# addon.net
KiCad netlist of a schematic drawn in EAGLE
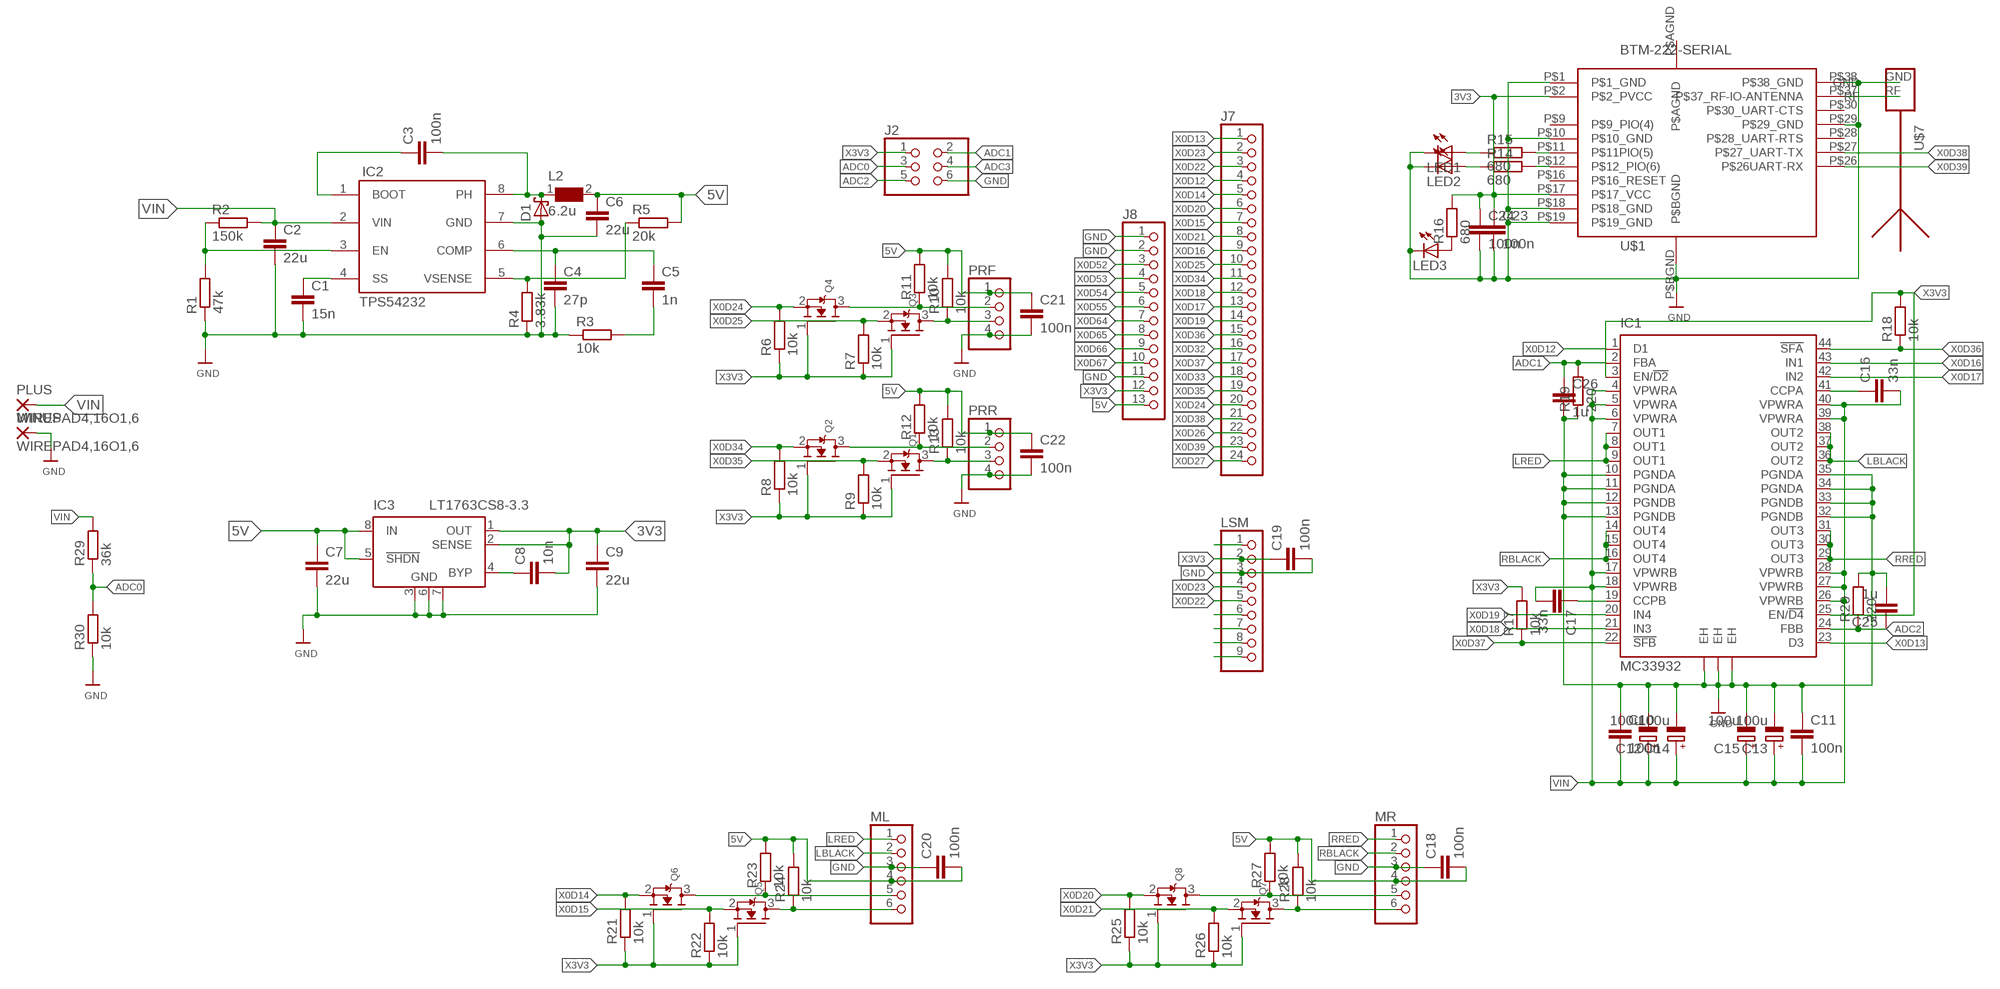
[diagram p0: schematic, sheet 1]

(export (version "E")
  (design (tool "Eeschema 10.0.6"))
  (components
    (comp (ref "C1")
      (value "15n")
      (footprint "eagle-import:C0603")
      (libsource (lib "eagle-import") (part "C-EUC0603"))
    )
    (comp (ref "C2")
      (value "22u")
      (footprint "eagle-import:C1210")
      (libsource (lib "eagle-import") (part "C-EUC1210"))
    )
    (comp (ref "C3")
      (value "100n")
      (footprint "eagle-import:C0603")
      (libsource (lib "eagle-import") (part "C-EUC0603"))
    )
    (comp (ref "C4")
      (value "27p")
      (footprint "eagle-import:C0603")
      (libsource (lib "eagle-import") (part "C-EUC0603"))
    )
    (comp (ref "C5")
      (value "1n")
      (footprint "eagle-import:C0603")
      (libsource (lib "eagle-import") (part "C-EUC0603"))
    )
    (comp (ref "C6")
      (value "22u")
      (footprint "eagle-import:C1206")
      (libsource (lib "eagle-import") (part "C-EUC1206"))
    )
    (comp (ref "C7")
      (value "22u")
      (footprint "eagle-import:C0603")
      (libsource (lib "eagle-import") (part "C-EUC0603"))
    )
    (comp (ref "C8")
      (value "10n")
      (footprint "eagle-import:C0603")
      (libsource (lib "eagle-import") (part "C-EUC0603"))
    )
    (comp (ref "C9")
      (value "22u")
      (footprint "eagle-import:C0603")
      (libsource (lib "eagle-import") (part "C-EUC0603"))
    )
    (comp (ref "C10")
      (value "100n")
      (footprint "eagle-import:C0603")
      (libsource (lib "eagle-import") (part "C-EUC0603"))
    )
    (comp (ref "C11")
      (value "100n")
      (footprint "eagle-import:C0603")
      (libsource (lib "eagle-import") (part "C-EUC0603"))
    )
    (comp (ref "C12")
      (value "100u")
      (footprint "eagle-import:D_7343-31R")
      (libsource (lib "eagle-import") (part "CPOL-EUD/7343-31R"))
    )
    (comp (ref "C13")
      (value "100u")
      (footprint "eagle-import:D_7343-31R")
      (libsource (lib "eagle-import") (part "CPOL-EUD/7343-31R"))
    )
    (comp (ref "C14")
      (value "100u")
      (footprint "eagle-import:D_7343-31R")
      (libsource (lib "eagle-import") (part "CPOL-EUD/7343-31R"))
    )
    (comp (ref "C15")
      (value "100u")
      (footprint "eagle-import:D_7343-31R")
      (libsource (lib "eagle-import") (part "CPOL-EUD/7343-31R"))
    )
    (comp (ref "C16")
      (value "33n")
      (footprint "eagle-import:C0603")
      (libsource (lib "eagle-import") (part "C-EUC0603"))
    )
    (comp (ref "C17")
      (value "33n")
      (footprint "eagle-import:C0603")
      (libsource (lib "eagle-import") (part "C-EUC0603"))
    )
    (comp (ref "C18")
      (value "100n")
      (footprint "eagle-import:C0603")
      (libsource (lib "eagle-import") (part "C-EUC0603"))
    )
    (comp (ref "C19")
      (value "100n")
      (footprint "eagle-import:C0603")
      (libsource (lib "eagle-import") (part "C-EUC0603"))
    )
    (comp (ref "C20")
      (value "100n")
      (footprint "eagle-import:C0603")
      (libsource (lib "eagle-import") (part "C-EUC0603"))
    )
    (comp (ref "C21")
      (value "100n")
      (footprint "eagle-import:C0603")
      (libsource (lib "eagle-import") (part "C-EUC0603"))
    )
    (comp (ref "C22")
      (value "100n")
      (footprint "eagle-import:C0603")
      (libsource (lib "eagle-import") (part "C-EUC0603"))
    )
    (comp (ref "C23")
      (value "100n")
      (footprint "eagle-import:C0603")
      (libsource (lib "eagle-import") (part "C-EUC0603"))
    )
    (comp (ref "C24")
      (value "100n")
      (footprint "eagle-import:C0603")
      (libsource (lib "eagle-import") (part "C-EUC0603"))
    )
    (comp (ref "C25")
      (value "1u")
      (footprint "eagle-import:C0603")
      (libsource (lib "eagle-import") (part "C-EUC0603"))
    )
    (comp (ref "C26")
      (value "1u")
      (footprint "eagle-import:C0603")
      (libsource (lib "eagle-import") (part "C-EUC0603"))
    )
    (comp (ref "D1")
      (value "SCHOTTKY-DIODESMD")
      (footprint "eagle-import:SMB")
      (libsource (lib "eagle-import") (part "SCHOTTKY-DIODESMD"))
    )
    (comp (ref "IC1")
      (value "MC33932")
      (footprint "eagle-import:HSOP44")
      (fields (field (name "MPN") "MC33932VW"))
      (libsource (lib "eagle-import") (part "MC33932"))
    )
    (comp (ref "IC2")
      (value "TPS54232")
      (footprint "eagle-import:YOURITRONICS_SO8")
      (libsource (lib "eagle-import") (part "YOURITRONICS_TPS54232"))
    )
    (comp (ref "IC3")
      (value "LT1763CS8-3.3")
      (footprint "eagle-import:SOIC8")
      (libsource (lib "eagle-import") (part "LT1763CS8-3.3"))
    )
    (comp (ref "J2")
      (value "PINHD-2X3")
      (footprint "eagle-import:2X03")
      (libsource (lib "eagle-import") (part "PINHD-2X3"))
    )
    (comp (ref "J7")
      (value "PINHD-1X24")
      (footprint "eagle-import:1X24")
      (libsource (lib "eagle-import") (part "PINHD-1X24"))
    )
    (comp (ref "J8")
      (value "PINHD-1X13")
      (footprint "eagle-import:1X13")
      (libsource (lib "eagle-import") (part "PINHD-1X13"))
    )
    (comp (ref "L2")
      (value "6.2u")
      (footprint "eagle-import:EAGLELIBRARY_WUERTH_ELEKTRONIK_EISOS_VERSION_6_WE-TPC_6823")
      (libsource (lib "eagle-import") (part "EAGLELIBRARY_WUERTH_ELEKTRONIK_EISOS_VERSION_6_WE-TPC_6823"))
    )
    (comp (ref "LED1")
      (value "LEDCHIPLED_0603")
      (footprint "eagle-import:CHIPLED_0603")
      (libsource (lib "eagle-import") (part "LEDCHIPLED_0603"))
    )
    (comp (ref "LED2")
      (value "LEDCHIPLED_0603")
      (footprint "eagle-import:CHIPLED_0603")
      (libsource (lib "eagle-import") (part "LEDCHIPLED_0603"))
    )
    (comp (ref "LED3")
      (value "LEDCHIPLED_0603")
      (footprint "eagle-import:CHIPLED_0603")
      (libsource (lib "eagle-import") (part "LEDCHIPLED_0603"))
    )
    (comp (ref "LSM")
      (value "PINHD-1X9")
      (footprint "eagle-import:1X09")
      (libsource (lib "eagle-import") (part "PINHD-1X9"))
    )
    (comp (ref "MINUS")
      (value "WIREPAD4,16O1,6")
      (footprint "eagle-import:4,16O1,6")
      (libsource (lib "eagle-import") (part "WIREPAD4,16O1,6"))
    )
    (comp (ref "ML")
      (value "PINHD-1X6")
      (footprint "eagle-import:1X06")
      (libsource (lib "eagle-import") (part "PINHD-1X6"))
    )
    (comp (ref "MR")
      (value "PINHD-1X6")
      (footprint "eagle-import:1X06")
      (libsource (lib "eagle-import") (part "PINHD-1X6"))
    )
    (comp (ref "PLUS")
      (value "WIREPAD4,16O1,6")
      (footprint "eagle-import:4,16O1,6")
      (libsource (lib "eagle-import") (part "WIREPAD4,16O1,6"))
    )
    (comp (ref "PRF")
      (value "PINHD-1X4")
      (footprint "eagle-import:1X04")
      (libsource (lib "eagle-import") (part "PINHD-1X4"))
    )
    (comp (ref "PRR")
      (value "PINHD-1X4")
      (footprint "eagle-import:1X04")
      (libsource (lib "eagle-import") (part "PINHD-1X4"))
    )
    (comp (ref "Q1")
      (value "MOSFET-NREFLOW")
      (footprint "eagle-import:SOT23-R")
      (libsource (lib "eagle-import") (part "MOSFET-NREFLOW"))
    )
    (comp (ref "Q2")
      (value "MOSFET-NREFLOW")
      (footprint "eagle-import:SOT23-R")
      (libsource (lib "eagle-import") (part "MOSFET-NREFLOW"))
    )
    (comp (ref "Q3")
      (value "MOSFET-NREFLOW")
      (footprint "eagle-import:SOT23-R")
      (libsource (lib "eagle-import") (part "MOSFET-NREFLOW"))
    )
    (comp (ref "Q4")
      (value "MOSFET-NREFLOW")
      (footprint "eagle-import:SOT23-R")
      (libsource (lib "eagle-import") (part "MOSFET-NREFLOW"))
    )
    (comp (ref "Q5")
      (value "MOSFET-NREFLOW")
      (footprint "eagle-import:SOT23-R")
      (libsource (lib "eagle-import") (part "MOSFET-NREFLOW"))
    )
    (comp (ref "Q6")
      (value "MOSFET-NREFLOW")
      (footprint "eagle-import:SOT23-R")
      (libsource (lib "eagle-import") (part "MOSFET-NREFLOW"))
    )
    (comp (ref "Q7")
      (value "MOSFET-NREFLOW")
      (footprint "eagle-import:SOT23-R")
      (libsource (lib "eagle-import") (part "MOSFET-NREFLOW"))
    )
    (comp (ref "Q8")
      (value "MOSFET-NREFLOW")
      (footprint "eagle-import:SOT23-R")
      (libsource (lib "eagle-import") (part "MOSFET-NREFLOW"))
    )
    (comp (ref "R1")
      (value "47k")
      (footprint "eagle-import:R0603")
      (libsource (lib "eagle-import") (part "R-EU_R0603"))
    )
    (comp (ref "R2")
      (value "150k")
      (footprint "eagle-import:R0603")
      (libsource (lib "eagle-import") (part "R-EU_R0603"))
    )
    (comp (ref "R3")
      (value "10k")
      (footprint "eagle-import:R0603")
      (libsource (lib "eagle-import") (part "R-EU_R0603"))
    )
    (comp (ref "R4")
      (value "3.83k")
      (footprint "eagle-import:R0603")
      (libsource (lib "eagle-import") (part "R-EU_R0603"))
    )
    (comp (ref "R5")
      (value "20k")
      (footprint "eagle-import:R0603")
      (libsource (lib "eagle-import") (part "R-EU_R0603"))
    )
    (comp (ref "R6")
      (value "10k")
      (footprint "eagle-import:R0603")
      (libsource (lib "eagle-import") (part "R-EU_R0603"))
    )
    (comp (ref "R7")
      (value "10k")
      (footprint "eagle-import:R0603")
      (libsource (lib "eagle-import") (part "R-EU_R0603"))
    )
    (comp (ref "R8")
      (value "10k")
      (footprint "eagle-import:R0603")
      (libsource (lib "eagle-import") (part "R-EU_R0603"))
    )
    (comp (ref "R9")
      (value "10k")
      (footprint "eagle-import:R0603")
      (libsource (lib "eagle-import") (part "R-EU_R0603"))
    )
    (comp (ref "R10")
      (value "10k")
      (footprint "eagle-import:R0603")
      (libsource (lib "eagle-import") (part "R-EU_R0603"))
    )
    (comp (ref "R11")
      (value "10k")
      (footprint "eagle-import:R0603")
      (libsource (lib "eagle-import") (part "R-EU_R0603"))
    )
    (comp (ref "R12")
      (value "10k")
      (footprint "eagle-import:R0603")
      (libsource (lib "eagle-import") (part "R-EU_R0603"))
    )
    (comp (ref "R13")
      (value "10k")
      (footprint "eagle-import:R0603")
      (libsource (lib "eagle-import") (part "R-EU_R0603"))
    )
    (comp (ref "R14")
      (value "680")
      (footprint "eagle-import:R0603")
      (libsource (lib "eagle-import") (part "R-EU_R0603"))
    )
    (comp (ref "R15")
      (value "680")
      (footprint "eagle-import:R0603")
      (libsource (lib "eagle-import") (part "R-EU_R0603"))
    )
    (comp (ref "R16")
      (value "680")
      (footprint "eagle-import:R0603")
      (libsource (lib "eagle-import") (part "R-EU_R0603"))
    )
    (comp (ref "R17")
      (value "10k")
      (footprint "eagle-import:R0603")
      (libsource (lib "eagle-import") (part "R-EU_R0603"))
    )
    (comp (ref "R18")
      (value "10k")
      (footprint "eagle-import:R0603")
      (libsource (lib "eagle-import") (part "R-EU_R0603"))
    )
    (comp (ref "R19")
      (value "220")
      (footprint "eagle-import:R0603")
      (libsource (lib "eagle-import") (part "R-EU_R0603"))
    )
    (comp (ref "R20")
      (value "220")
      (footprint "eagle-import:R0603")
      (libsource (lib "eagle-import") (part "R-EU_R0603"))
    )
    (comp (ref "R21")
      (value "10k")
      (footprint "eagle-import:R0603")
      (libsource (lib "eagle-import") (part "R-EU_R0603"))
    )
    (comp (ref "R22")
      (value "10k")
      (footprint "eagle-import:R0603")
      (libsource (lib "eagle-import") (part "R-EU_R0603"))
    )
    (comp (ref "R23")
      (value "10k")
      (footprint "eagle-import:R0603")
      (libsource (lib "eagle-import") (part "R-EU_R0603"))
    )
    (comp (ref "R24")
      (value "10k")
      (footprint "eagle-import:R0603")
      (libsource (lib "eagle-import") (part "R-EU_R0603"))
    )
    (comp (ref "R25")
      (value "10k")
      (footprint "eagle-import:R0603")
      (libsource (lib "eagle-import") (part "R-EU_R0603"))
    )
    (comp (ref "R26")
      (value "10k")
      (footprint "eagle-import:R0603")
      (libsource (lib "eagle-import") (part "R-EU_R0603"))
    )
    (comp (ref "R27")
      (value "10k")
      (footprint "eagle-import:R0603")
      (libsource (lib "eagle-import") (part "R-EU_R0603"))
    )
    (comp (ref "R28")
      (value "10k")
      (footprint "eagle-import:R0603")
      (libsource (lib "eagle-import") (part "R-EU_R0603"))
    )
    (comp (ref "R29")
      (value "36k")
      (footprint "eagle-import:R0603")
      (libsource (lib "eagle-import") (part "R-EU_R0603"))
    )
    (comp (ref "R30")
      (value "10k")
      (footprint "eagle-import:R0603")
      (libsource (lib "eagle-import") (part "R-EU_R0603"))
    )
    (comp (ref "U$1")
      (value "BTM-222-SERIAL")
      (footprint "eagle-import:BTM-222")
      (libsource (lib "eagle-import") (part "BTM-222-SERIAL"))
    )
    (comp (ref "U$7")
      (value "ANTENNA_1RIGHT")
      (footprint "eagle-import:SWRA117D_RIGHT")
      (libsource (lib "eagle-import") (part "ANTENNA_1RIGHT"))
    )
  )
  (nets
    (net (code "1") (name "/P$AGND") (class "Default")
      (node (ref "U$1") (pin "P$AGND") (pinfunction "P$AGND_P$AGND") (pintype "power_in"))
    )
    (net (code "2") (name "3V3") (class "Default")
      (node (ref "C23") (pin "1") (pinfunction "1_1") (pintype "passive"))
      (node (ref "C24") (pin "1") (pinfunction "1_1") (pintype "passive"))
      (node (ref "C8") (pin "2") (pinfunction "2_2") (pintype "passive"))
      (node (ref "C9") (pin "1") (pinfunction "1_1") (pintype "passive"))
      (node (ref "IC3") (pin "1") (pinfunction "OUT_1") (pintype "passive"))
      (node (ref "IC3") (pin "2") (pinfunction "SENSE_2") (pintype "input"))
      (node (ref "R16") (pin "2") (pinfunction "2_2") (pintype "passive"))
      (node (ref "U$1") (pin "P$17") (pinfunction "P$17_VCC_P$17") (pintype "power_in"))
      (node (ref "U$1") (pin "P$2") (pinfunction "P$2_PVCC_P$2") (pintype "power_in"))
    )
    (net (code "3") (name "5V") (class "Default")
      (node (ref "C18") (pin "2") (pinfunction "2_2") (pintype "passive"))
      (node (ref "C20") (pin "2") (pinfunction "2_2") (pintype "passive"))
      (node (ref "C21") (pin "1") (pinfunction "1_1") (pintype "passive"))
      (node (ref "C22") (pin "1") (pinfunction "1_1") (pintype "passive"))
      (node (ref "C6") (pin "1") (pinfunction "1_1") (pintype "passive"))
      (node (ref "C7") (pin "1") (pinfunction "1_1") (pintype "passive"))
      (node (ref "IC3") (pin "5") (pinfunction "~{SHDN}_5") (pintype "input"))
      (node (ref "IC3") (pin "8") (pinfunction "IN_8") (pintype "input"))
      (node (ref "J8") (pin "13") (pinfunction "13_13") (pintype "passive"))
      (node (ref "L2") (pin "2") (pinfunction "2_2") (pintype "passive"))
      (node (ref "ML") (pin "4") (pinfunction "4_4") (pintype "passive"))
      (node (ref "MR") (pin "4") (pinfunction "4_4") (pintype "passive"))
      (node (ref "PRF") (pin "1") (pinfunction "1_1") (pintype "passive"))
      (node (ref "PRR") (pin "1") (pinfunction "1_1") (pintype "passive"))
      (node (ref "R10") (pin "2") (pinfunction "2_2") (pintype "passive"))
      (node (ref "R11") (pin "2") (pinfunction "2_2") (pintype "passive"))
      (node (ref "R12") (pin "2") (pinfunction "2_2") (pintype "passive"))
      (node (ref "R13") (pin "2") (pinfunction "2_2") (pintype "passive"))
      (node (ref "R23") (pin "2") (pinfunction "2_2") (pintype "passive"))
      (node (ref "R24") (pin "2") (pinfunction "2_2") (pintype "passive"))
      (node (ref "R27") (pin "2") (pinfunction "2_2") (pintype "passive"))
      (node (ref "R28") (pin "2") (pinfunction "2_2") (pintype "passive"))
      (node (ref "R5") (pin "2") (pinfunction "2_2") (pintype "passive"))
    )
    (net (code "4") (name "ADC0") (class "Default")
      (node (ref "J2") (pin "3") (pinfunction "3_3") (pintype "passive"))
      (node (ref "R29") (pin "1") (pinfunction "1_1") (pintype "passive"))
      (node (ref "R30") (pin "2") (pinfunction "2_2") (pintype "passive"))
    )
    (net (code "5") (name "ADC1") (class "Default")
      (node (ref "C26") (pin "1") (pinfunction "1_1") (pintype "passive"))
      (node (ref "IC1") (pin "2") (pinfunction "FBA_2") (pintype "output"))
      (node (ref "J2") (pin "2") (pinfunction "2_2") (pintype "passive"))
      (node (ref "R19") (pin "2") (pinfunction "2_2") (pintype "passive"))
    )
    (net (code "6") (name "ADC2") (class "Default")
      (node (ref "C25") (pin "1") (pinfunction "1_1") (pintype "passive"))
      (node (ref "IC1") (pin "24") (pinfunction "FBB_24") (pintype "output"))
      (node (ref "J2") (pin "5") (pinfunction "5_5") (pintype "passive"))
      (node (ref "R20") (pin "1") (pinfunction "1_1") (pintype "passive"))
    )
    (net (code "7") (name "ADC3") (class "Default")
      (node (ref "J2") (pin "4") (pinfunction "4_4") (pintype "passive"))
    )
    (net (code "8") (name "GND") (class "Default")
      (node (ref "C1") (pin "2") (pinfunction "2_2") (pintype "passive"))
      (node (ref "C10") (pin "1") (pinfunction "1_1") (pintype "passive"))
      (node (ref "C11") (pin "1") (pinfunction "1_1") (pintype "passive"))
      (node (ref "C12") (pin "-") (pinfunction "-_-") (pintype "passive"))
      (node (ref "C13") (pin "-") (pinfunction "-_-") (pintype "passive"))
      (node (ref "C14") (pin "-") (pinfunction "-_-") (pintype "passive"))
      (node (ref "C15") (pin "-") (pinfunction "-_-") (pintype "passive"))
      (node (ref "C18") (pin "1") (pinfunction "1_1") (pintype "passive"))
      (node (ref "C19") (pin "2") (pinfunction "2_2") (pintype "passive"))
      (node (ref "C2") (pin "2") (pinfunction "2_2") (pintype "passive"))
      (node (ref "C20") (pin "1") (pinfunction "1_1") (pintype "passive"))
      (node (ref "C21") (pin "2") (pinfunction "2_2") (pintype "passive"))
      (node (ref "C22") (pin "2") (pinfunction "2_2") (pintype "passive"))
      (node (ref "C23") (pin "2") (pinfunction "2_2") (pintype "passive"))
      (node (ref "C24") (pin "2") (pinfunction "2_2") (pintype "passive"))
      (node (ref "C25") (pin "2") (pinfunction "2_2") (pintype "passive"))
      (node (ref "C26") (pin "2") (pinfunction "2_2") (pintype "passive"))
      (node (ref "C4") (pin "2") (pinfunction "2_2") (pintype "passive"))
      (node (ref "C6") (pin "2") (pinfunction "2_2") (pintype "passive"))
      (node (ref "C7") (pin "2") (pinfunction "2_2") (pintype "passive"))
      (node (ref "C9") (pin "2") (pinfunction "2_2") (pintype "passive"))
      (node (ref "D1") (pin "A") (pinfunction "A_A") (pintype "passive"))
      (node (ref "IC1") (pin "10") (pinfunction "PGNDA_10") (pintype "power_in"))
      (node (ref "IC1") (pin "11") (pinfunction "PGNDA_11") (pintype "power_in"))
      (node (ref "IC1") (pin "12") (pinfunction "PGNDB_12") (pintype "power_in"))
      (node (ref "IC1") (pin "13") (pinfunction "PGNDB_13") (pintype "power_in"))
      (node (ref "IC1") (pin "32") (pinfunction "PGNDB_32") (pintype "power_in"))
      (node (ref "IC1") (pin "33") (pinfunction "PGNDB_33") (pintype "power_in"))
      (node (ref "IC1") (pin "34") (pinfunction "PGNDA_34") (pintype "power_in"))
      (node (ref "IC1") (pin "35") (pinfunction "PGNDA_35") (pintype "power_in"))
      (node (ref "IC1") (pin "EH@1") (pinfunction "EH_EH@1") (pintype "passive"))
      (node (ref "IC1") (pin "EH@2") (pinfunction "EH_EH@2") (pintype "passive"))
      (node (ref "IC1") (pin "EH@3") (pinfunction "EH_EH@3") (pintype "passive"))
      (node (ref "IC2") (pin "7") (pinfunction "GND_7") (pintype "bidirectional"))
      (node (ref "IC3") (pin "3") (pinfunction "GND_3") (pintype "power_in"))
      (node (ref "IC3") (pin "6") (pinfunction "GND_6") (pintype "power_in"))
      (node (ref "IC3") (pin "7") (pinfunction "GND_7") (pintype "power_in"))
      (node (ref "J2") (pin "6") (pinfunction "6_6") (pintype "passive"))
      (node (ref "J8") (pin "1") (pinfunction "1_1") (pintype "passive"))
      (node (ref "J8") (pin "11") (pinfunction "11_11") (pintype "passive"))
      (node (ref "J8") (pin "2") (pinfunction "2_2") (pintype "passive"))
      (node (ref "LED1") (pin "C") (pinfunction "C_C") (pintype "passive"))
      (node (ref "LED2") (pin "C") (pinfunction "C_C") (pintype "passive"))
      (node (ref "LED3") (pin "C") (pinfunction "C_C") (pintype "passive"))
      (node (ref "LSM") (pin "3") (pinfunction "3_3") (pintype "passive"))
      (node (ref "MINUS") (pin "1") (pinfunction "P_1") (pintype "passive"))
      (node (ref "ML") (pin "3") (pinfunction "3_3") (pintype "passive"))
      (node (ref "MR") (pin "3") (pinfunction "3_3") (pintype "passive"))
      (node (ref "PRF") (pin "4") (pinfunction "4_4") (pintype "passive"))
      (node (ref "PRR") (pin "4") (pinfunction "4_4") (pintype "passive"))
      (node (ref "R1") (pin "1") (pinfunction "1_1") (pintype "passive"))
      (node (ref "R19") (pin "1") (pinfunction "1_1") (pintype "passive"))
      (node (ref "R20") (pin "2") (pinfunction "2_2") (pintype "passive"))
      (node (ref "R3") (pin "1") (pinfunction "1_1") (pintype "passive"))
      (node (ref "R30") (pin "1") (pinfunction "1_1") (pintype "passive"))
      (node (ref "R4") (pin "1") (pinfunction "1_1") (pintype "passive"))
      (node (ref "U$1") (pin "P$1") (pinfunction "P$1_GND_P$1") (pintype "power_in"))
      (node (ref "U$1") (pin "P$10") (pinfunction "P$10_GND_P$10") (pintype "power_in"))
      (node (ref "U$1") (pin "P$18") (pinfunction "P$18_GND_P$18") (pintype "power_in"))
      (node (ref "U$1") (pin "P$19") (pinfunction "P$19_GND_P$19") (pintype "power_in"))
      (node (ref "U$1") (pin "P$29") (pinfunction "P$29_GND_P$29") (pintype "power_in"))
      (node (ref "U$1") (pin "P$38") (pinfunction "P$38_GND_P$38") (pintype "power_in"))
      (node (ref "U$1") (pin "P$BGND") (pinfunction "P$BGND_P$BGND") (pintype "power_in"))
      (node (ref "U$7") (pin "GND") (pinfunction "GND_GND") (pintype "passive"))
    )
    (net (code "9") (name "LBLACK") (class "Default")
      (node (ref "IC1") (pin "36") (pinfunction "OUT2_36") (pintype "output"))
      (node (ref "IC1") (pin "37") (pinfunction "OUT2_37") (pintype "passive"))
      (node (ref "IC1") (pin "38") (pinfunction "OUT2_38") (pintype "passive"))
      (node (ref "ML") (pin "2") (pinfunction "2_2") (pintype "passive"))
    )
    (net (code "10") (name "LRED") (class "Default")
      (node (ref "IC1") (pin "7") (pinfunction "OUT1_7") (pintype "output"))
      (node (ref "IC1") (pin "8") (pinfunction "OUT1_8") (pintype "passive"))
      (node (ref "IC1") (pin "9") (pinfunction "OUT1_9") (pintype "passive"))
      (node (ref "ML") (pin "1") (pinfunction "1_1") (pintype "passive"))
    )
    (net (code "11") (name "Net-(C5-Pad2)") (class "Default")
      (node (ref "C5") (pin "2") (pinfunction "2_2") (pintype "passive"))
      (node (ref "R3") (pin "2") (pinfunction "2_2") (pintype "passive"))
    )
    (net (code "12") (name "Net-(IC1-CCPA)") (class "Default")
      (node (ref "C16") (pin "1") (pinfunction "1_1") (pintype "passive"))
      (node (ref "IC1") (pin "41") (pinfunction "CCPA_41") (pintype "output"))
    )
    (net (code "13") (name "Net-(IC1-CCPB)") (class "Default")
      (node (ref "C17") (pin "1") (pinfunction "1_1") (pintype "passive"))
      (node (ref "IC1") (pin "19") (pinfunction "CCPB_19") (pintype "output"))
    )
    (net (code "14") (name "Net-(IC2-BOOT)") (class "Default")
      (node (ref "C3") (pin "1") (pinfunction "1_1") (pintype "passive"))
      (node (ref "IC2") (pin "1") (pinfunction "BOOT_1") (pintype "bidirectional"))
    )
    (net (code "15") (name "Net-(IC2-COMP)") (class "Default")
      (node (ref "C4") (pin "1") (pinfunction "1_1") (pintype "passive"))
      (node (ref "C5") (pin "1") (pinfunction "1_1") (pintype "passive"))
      (node (ref "IC2") (pin "6") (pinfunction "COMP_6") (pintype "bidirectional"))
    )
    (net (code "16") (name "Net-(IC2-EN)") (class "Default")
      (node (ref "IC2") (pin "3") (pinfunction "EN_3") (pintype "bidirectional"))
      (node (ref "R1") (pin "2") (pinfunction "2_2") (pintype "passive"))
      (node (ref "R2") (pin "1") (pinfunction "1_1") (pintype "passive"))
    )
    (net (code "17") (name "Net-(IC2-PH)") (class "Default")
      (node (ref "C3") (pin "2") (pinfunction "2_2") (pintype "passive"))
      (node (ref "D1") (pin "C") (pinfunction "C_C") (pintype "passive"))
      (node (ref "IC2") (pin "8") (pinfunction "PH_8") (pintype "bidirectional"))
      (node (ref "L2") (pin "1") (pinfunction "1_1") (pintype "passive"))
    )
    (net (code "18") (name "Net-(IC2-SS)") (class "Default")
      (node (ref "C1") (pin "1") (pinfunction "1_1") (pintype "passive"))
      (node (ref "IC2") (pin "4") (pinfunction "SS_4") (pintype "bidirectional"))
    )
    (net (code "19") (name "Net-(IC2-VSENSE)") (class "Default")
      (node (ref "IC2") (pin "5") (pinfunction "VSENSE_5") (pintype "bidirectional"))
      (node (ref "R4") (pin "2") (pinfunction "2_2") (pintype "passive"))
      (node (ref "R5") (pin "1") (pinfunction "1_1") (pintype "passive"))
    )
    (net (code "20") (name "Net-(IC3-BYP)") (class "Default")
      (node (ref "C8") (pin "1") (pinfunction "1_1") (pintype "passive"))
      (node (ref "IC3") (pin "4") (pinfunction "BYP_4") (pintype "input"))
    )
    (net (code "21") (name "Net-(LED1-PadA)") (class "Default")
      (node (ref "LED1") (pin "A") (pinfunction "A_A") (pintype "passive"))
      (node (ref "R15") (pin "1") (pinfunction "1_1") (pintype "passive"))
    )
    (net (code "22") (name "Net-(LED2-PadA)") (class "Default")
      (node (ref "LED2") (pin "A") (pinfunction "A_A") (pintype "passive"))
      (node (ref "R14") (pin "1") (pinfunction "1_1") (pintype "passive"))
    )
    (net (code "23") (name "Net-(LED3-PadA)") (class "Default")
      (node (ref "LED3") (pin "A") (pinfunction "A_A") (pintype "passive"))
      (node (ref "R16") (pin "1") (pinfunction "1_1") (pintype "passive"))
    )
    (net (code "24") (name "Net-(Q1-D)") (class "Default")
      (node (ref "PRR") (pin "3") (pinfunction "3_3") (pintype "passive"))
      (node (ref "Q1") (pin "3") (pinfunction "D_3") (pintype "bidirectional"))
      (node (ref "R13") (pin "1") (pinfunction "1_1") (pintype "passive"))
    )
    (net (code "25") (name "Net-(Q2-D)") (class "Default")
      (node (ref "PRR") (pin "2") (pinfunction "2_2") (pintype "passive"))
      (node (ref "Q2") (pin "3") (pinfunction "D_3") (pintype "bidirectional"))
      (node (ref "R12") (pin "1") (pinfunction "1_1") (pintype "passive"))
    )
    (net (code "26") (name "Net-(Q3-D)") (class "Default")
      (node (ref "PRF") (pin "3") (pinfunction "3_3") (pintype "passive"))
      (node (ref "Q3") (pin "3") (pinfunction "D_3") (pintype "bidirectional"))
      (node (ref "R10") (pin "1") (pinfunction "1_1") (pintype "passive"))
    )
    (net (code "27") (name "Net-(Q4-D)") (class "Default")
      (node (ref "PRF") (pin "2") (pinfunction "2_2") (pintype "passive"))
      (node (ref "Q4") (pin "3") (pinfunction "D_3") (pintype "bidirectional"))
      (node (ref "R11") (pin "1") (pinfunction "1_1") (pintype "passive"))
    )
    (net (code "28") (name "Net-(Q5-D)") (class "Default")
      (node (ref "ML") (pin "6") (pinfunction "6_6") (pintype "passive"))
      (node (ref "Q5") (pin "3") (pinfunction "D_3") (pintype "bidirectional"))
      (node (ref "R24") (pin "1") (pinfunction "1_1") (pintype "passive"))
    )
    (net (code "29") (name "Net-(Q6-D)") (class "Default")
      (node (ref "ML") (pin "5") (pinfunction "5_5") (pintype "passive"))
      (node (ref "Q6") (pin "3") (pinfunction "D_3") (pintype "bidirectional"))
      (node (ref "R23") (pin "1") (pinfunction "1_1") (pintype "passive"))
    )
    (net (code "30") (name "Net-(Q7-D)") (class "Default")
      (node (ref "MR") (pin "6") (pinfunction "6_6") (pintype "passive"))
      (node (ref "Q7") (pin "3") (pinfunction "D_3") (pintype "bidirectional"))
      (node (ref "R28") (pin "1") (pinfunction "1_1") (pintype "passive"))
    )
    (net (code "31") (name "Net-(Q8-D)") (class "Default")
      (node (ref "MR") (pin "5") (pinfunction "5_5") (pintype "passive"))
      (node (ref "Q8") (pin "3") (pinfunction "D_3") (pintype "bidirectional"))
      (node (ref "R27") (pin "1") (pinfunction "1_1") (pintype "passive"))
    )
    (net (code "32") (name "Net-(U$1-P$11PIO(5))") (class "Default")
      (node (ref "R15") (pin "2") (pinfunction "2_2") (pintype "passive"))
      (node (ref "U$1") (pin "P$11") (pinfunction "P$11PIO(5)_P$11") (pintype "bidirectional"))
    )
    (net (code "33") (name "Net-(U$1-P$12_PIO(6))") (class "Default")
      (node (ref "R14") (pin "2") (pinfunction "2_2") (pintype "passive"))
      (node (ref "U$1") (pin "P$12") (pinfunction "P$12_PIO(6)_P$12") (pintype "bidirectional"))
    )
    (net (code "34") (name "Net-(U$1-P$37_RF-IO-ANTENNA)") (class "Default")
      (node (ref "U$1") (pin "P$37") (pinfunction "P$37_RF-IO-ANTENNA_P$37") (pintype "bidirectional"))
      (node (ref "U$7") (pin "RF") (pinfunction "RF_RF") (pintype "bidirectional"))
    )
    (net (code "35") (name "RBLACK") (class "Default")
      (node (ref "IC1") (pin "14") (pinfunction "OUT4_14") (pintype "output"))
      (node (ref "IC1") (pin "15") (pinfunction "OUT4_15") (pintype "passive"))
      (node (ref "IC1") (pin "16") (pinfunction "OUT4_16") (pintype "passive"))
      (node (ref "MR") (pin "2") (pinfunction "2_2") (pintype "passive"))
    )
    (net (code "36") (name "RRED") (class "Default")
      (node (ref "IC1") (pin "29") (pinfunction "OUT3_29") (pintype "output"))
      (node (ref "IC1") (pin "30") (pinfunction "OUT3_30") (pintype "passive"))
      (node (ref "IC1") (pin "31") (pinfunction "OUT3_31") (pintype "passive"))
      (node (ref "MR") (pin "1") (pinfunction "1_1") (pintype "passive"))
    )
    (net (code "37") (name "VIN") (class "Default")
      (node (ref "C10") (pin "2") (pinfunction "2_2") (pintype "passive"))
      (node (ref "C11") (pin "2") (pinfunction "2_2") (pintype "passive"))
      (node (ref "C12") (pin "+") (pinfunction "+_+") (pintype "passive"))
      (node (ref "C13") (pin "+") (pinfunction "+_+") (pintype "passive"))
      (node (ref "C14") (pin "+") (pinfunction "+_+") (pintype "passive"))
      (node (ref "C15") (pin "+") (pinfunction "+_+") (pintype "passive"))
      (node (ref "C16") (pin "2") (pinfunction "2_2") (pintype "passive"))
      (node (ref "C17") (pin "2") (pinfunction "2_2") (pintype "passive"))
      (node (ref "C2") (pin "1") (pinfunction "1_1") (pintype "passive"))
      (node (ref "IC1") (pin "17") (pinfunction "VPWRB_17") (pintype "input"))
      (node (ref "IC1") (pin "18") (pinfunction "VPWRB_18") (pintype "input"))
      (node (ref "IC1") (pin "26") (pinfunction "VPWRB_26") (pintype "input"))
      (node (ref "IC1") (pin "27") (pinfunction "VPWRB_27") (pintype "input"))
      (node (ref "IC1") (pin "28") (pinfunction "VPWRB_28") (pintype "input"))
      (node (ref "IC1") (pin "39") (pinfunction "VPWRA_39") (pintype "input"))
      (node (ref "IC1") (pin "4") (pinfunction "VPWRA_4") (pintype "input"))
      (node (ref "IC1") (pin "40") (pinfunction "VPWRA_40") (pintype "input"))
      (node (ref "IC1") (pin "5") (pinfunction "VPWRA_5") (pintype "input"))
      (node (ref "IC1") (pin "6") (pinfunction "VPWRA_6") (pintype "input"))
      (node (ref "IC2") (pin "2") (pinfunction "VIN_2") (pintype "bidirectional"))
      (node (ref "PLUS") (pin "1") (pinfunction "P_1") (pintype "passive"))
      (node (ref "R2") (pin "2") (pinfunction "2_2") (pintype "passive"))
      (node (ref "R29") (pin "2") (pinfunction "2_2") (pintype "passive"))
    )
    (net (code "38") (name "X0D12") (class "Default")
      (node (ref "IC1") (pin "1") (pinfunction "D1_1") (pintype "input"))
      (node (ref "J7") (pin "4") (pinfunction "4_4") (pintype "passive"))
    )
    (net (code "39") (name "X0D13") (class "Default")
      (node (ref "IC1") (pin "23") (pinfunction "D3_23") (pintype "input"))
      (node (ref "J7") (pin "1") (pinfunction "1_1") (pintype "passive"))
    )
    (net (code "40") (name "X0D14") (class "Default")
      (node (ref "J7") (pin "5") (pinfunction "5_5") (pintype "passive"))
      (node (ref "Q6") (pin "2") (pinfunction "S_2") (pintype "bidirectional"))
      (node (ref "R21") (pin "2") (pinfunction "2_2") (pintype "passive"))
    )
    (net (code "41") (name "X0D15") (class "Default")
      (node (ref "J7") (pin "7") (pinfunction "7_7") (pintype "passive"))
      (node (ref "Q5") (pin "2") (pinfunction "S_2") (pintype "bidirectional"))
      (node (ref "R22") (pin "2") (pinfunction "2_2") (pintype "passive"))
    )
    (net (code "42") (name "X0D16") (class "Default")
      (node (ref "IC1") (pin "43") (pinfunction "IN1_43") (pintype "input"))
      (node (ref "J7") (pin "9") (pinfunction "9_9") (pintype "passive"))
    )
    (net (code "43") (name "X0D17") (class "Default")
      (node (ref "IC1") (pin "42") (pinfunction "IN2_42") (pintype "input"))
      (node (ref "J7") (pin "13") (pinfunction "13_13") (pintype "passive"))
    )
    (net (code "44") (name "X0D18") (class "Default")
      (node (ref "IC1") (pin "21") (pinfunction "IN3_21") (pintype "input"))
      (node (ref "J7") (pin "12") (pinfunction "12_12") (pintype "passive"))
    )
    (net (code "45") (name "X0D19") (class "Default")
      (node (ref "IC1") (pin "20") (pinfunction "IN4_20") (pintype "input"))
      (node (ref "J7") (pin "14") (pinfunction "14_14") (pintype "passive"))
    )
    (net (code "46") (name "X0D20") (class "Default")
      (node (ref "J7") (pin "6") (pinfunction "6_6") (pintype "passive"))
      (node (ref "Q8") (pin "2") (pinfunction "S_2") (pintype "bidirectional"))
      (node (ref "R25") (pin "2") (pinfunction "2_2") (pintype "passive"))
    )
    (net (code "47") (name "X0D21") (class "Default")
      (node (ref "J7") (pin "8") (pinfunction "8_8") (pintype "passive"))
      (node (ref "Q7") (pin "2") (pinfunction "S_2") (pintype "bidirectional"))
      (node (ref "R26") (pin "2") (pinfunction "2_2") (pintype "passive"))
    )
    (net (code "48") (name "X0D22") (class "Default")
      (node (ref "J7") (pin "3") (pinfunction "3_3") (pintype "passive"))
      (node (ref "LSM") (pin "5") (pinfunction "5_5") (pintype "passive"))
    )
    (net (code "49") (name "X0D23") (class "Default")
      (node (ref "J7") (pin "2") (pinfunction "2_2") (pintype "passive"))
      (node (ref "LSM") (pin "4") (pinfunction "4_4") (pintype "passive"))
    )
    (net (code "50") (name "X0D24") (class "Default")
      (node (ref "J7") (pin "20") (pinfunction "20_20") (pintype "passive"))
      (node (ref "Q4") (pin "2") (pinfunction "S_2") (pintype "bidirectional"))
      (node (ref "R6") (pin "2") (pinfunction "2_2") (pintype "passive"))
    )
    (net (code "51") (name "X0D25") (class "Default")
      (node (ref "J7") (pin "10") (pinfunction "10_10") (pintype "passive"))
      (node (ref "Q3") (pin "2") (pinfunction "S_2") (pintype "bidirectional"))
      (node (ref "R7") (pin "2") (pinfunction "2_2") (pintype "passive"))
    )
    (net (code "52") (name "X0D26") (class "Default")
      (node (ref "J7") (pin "22") (pinfunction "22_22") (pintype "passive"))
    )
    (net (code "53") (name "X0D27") (class "Default")
      (node (ref "J7") (pin "24") (pinfunction "24_24") (pintype "passive"))
    )
    (net (code "54") (name "X0D32") (class "Default")
      (node (ref "J7") (pin "16") (pinfunction "16_16") (pintype "passive"))
    )
    (net (code "55") (name "X0D33") (class "Default")
      (node (ref "J7") (pin "18") (pinfunction "18_18") (pintype "passive"))
    )
    (net (code "56") (name "X0D34") (class "Default")
      (node (ref "J7") (pin "11") (pinfunction "11_11") (pintype "passive"))
      (node (ref "Q2") (pin "2") (pinfunction "S_2") (pintype "bidirectional"))
      (node (ref "R8") (pin "2") (pinfunction "2_2") (pintype "passive"))
    )
    (net (code "57") (name "X0D35") (class "Default")
      (node (ref "J7") (pin "19") (pinfunction "19_19") (pintype "passive"))
      (node (ref "Q1") (pin "2") (pinfunction "S_2") (pintype "bidirectional"))
      (node (ref "R9") (pin "2") (pinfunction "2_2") (pintype "passive"))
    )
    (net (code "58") (name "X0D36") (class "Default")
      (node (ref "IC1") (pin "44") (pinfunction "~{SFA}_44") (pintype "open_collector"))
      (node (ref "J7") (pin "15") (pinfunction "15_15") (pintype "passive"))
      (node (ref "R18") (pin "1") (pinfunction "1_1") (pintype "passive"))
    )
    (net (code "59") (name "X0D37") (class "Default")
      (node (ref "IC1") (pin "22") (pinfunction "~{SFB}_22") (pintype "open_collector"))
      (node (ref "J7") (pin "17") (pinfunction "17_17") (pintype "passive"))
      (node (ref "R17") (pin "1") (pinfunction "1_1") (pintype "passive"))
    )
    (net (code "60") (name "X0D38") (class "Default")
      (node (ref "J7") (pin "21") (pinfunction "21_21") (pintype "passive"))
      (node (ref "U$1") (pin "P$27") (pinfunction "P$27_UART-TX_P$27") (pintype "output"))
    )
    (net (code "61") (name "X0D39") (class "Default")
      (node (ref "J7") (pin "23") (pinfunction "23_23") (pintype "passive"))
      (node (ref "U$1") (pin "P$26") (pinfunction "P$26UART-RX_P$26") (pintype "input"))
    )
    (net (code "62") (name "X0D52") (class "Default")
      (node (ref "J8") (pin "3") (pinfunction "3_3") (pintype "passive"))
    )
    (net (code "63") (name "X0D53") (class "Default")
      (node (ref "J8") (pin "4") (pinfunction "4_4") (pintype "passive"))
    )
    (net (code "64") (name "X0D54") (class "Default")
      (node (ref "J8") (pin "5") (pinfunction "5_5") (pintype "passive"))
    )
    (net (code "65") (name "X0D55") (class "Default")
      (node (ref "J8") (pin "6") (pinfunction "6_6") (pintype "passive"))
    )
    (net (code "66") (name "X0D64") (class "Default")
      (node (ref "J8") (pin "7") (pinfunction "7_7") (pintype "passive"))
    )
    (net (code "67") (name "X0D65") (class "Default")
      (node (ref "J8") (pin "8") (pinfunction "8_8") (pintype "passive"))
    )
    (net (code "68") (name "X0D66") (class "Default")
      (node (ref "J8") (pin "9") (pinfunction "9_9") (pintype "passive"))
    )
    (net (code "69") (name "X0D67") (class "Default")
      (node (ref "J8") (pin "10") (pinfunction "10_10") (pintype "passive"))
    )
    (net (code "70") (name "X3V3") (class "Default")
      (node (ref "C19") (pin "1") (pinfunction "1_1") (pintype "passive"))
      (node (ref "IC1") (pin "25") (pinfunction "EN/~{D4}_25") (pintype "input"))
      (node (ref "IC1") (pin "3") (pinfunction "EN/~{D2}_3") (pintype "input"))
      (node (ref "J2") (pin "1") (pinfunction "1_1") (pintype "passive"))
      (node (ref "J8") (pin "12") (pinfunction "12_12") (pintype "passive"))
      (node (ref "LSM") (pin "2") (pinfunction "2_2") (pintype "passive"))
      (node (ref "Q1") (pin "1") (pinfunction "G_1") (pintype "bidirectional"))
      (node (ref "Q2") (pin "1") (pinfunction "G_1") (pintype "bidirectional"))
      (node (ref "Q3") (pin "1") (pinfunction "G_1") (pintype "bidirectional"))
      (node (ref "Q4") (pin "1") (pinfunction "G_1") (pintype "bidirectional"))
      (node (ref "Q5") (pin "1") (pinfunction "G_1") (pintype "bidirectional"))
      (node (ref "Q6") (pin "1") (pinfunction "G_1") (pintype "bidirectional"))
      (node (ref "Q7") (pin "1") (pinfunction "G_1") (pintype "bidirectional"))
      (node (ref "Q8") (pin "1") (pinfunction "G_1") (pintype "bidirectional"))
      (node (ref "R17") (pin "2") (pinfunction "2_2") (pintype "passive"))
      (node (ref "R18") (pin "2") (pinfunction "2_2") (pintype "passive"))
      (node (ref "R21") (pin "1") (pinfunction "1_1") (pintype "passive"))
      (node (ref "R22") (pin "1") (pinfunction "1_1") (pintype "passive"))
      (node (ref "R25") (pin "1") (pinfunction "1_1") (pintype "passive"))
      (node (ref "R26") (pin "1") (pinfunction "1_1") (pintype "passive"))
      (node (ref "R6") (pin "1") (pinfunction "1_1") (pintype "passive"))
      (node (ref "R7") (pin "1") (pinfunction "1_1") (pintype "passive"))
      (node (ref "R8") (pin "1") (pinfunction "1_1") (pintype "passive"))
      (node (ref "R9") (pin "1") (pinfunction "1_1") (pintype "passive"))
    )
    (net (code "71") (name "unconnected-(LSM-Pad1)") (class "Default")
      (node (ref "LSM") (pin "1") (pinfunction "1_1") (pintype "passive"))
    )
    (net (code "72") (name "unconnected-(LSM-Pad6)") (class "Default")
      (node (ref "LSM") (pin "6") (pinfunction "6_6") (pintype "passive"))
    )
    (net (code "73") (name "unconnected-(LSM-Pad7)") (class "Default")
      (node (ref "LSM") (pin "7") (pinfunction "7_7") (pintype "passive"))
    )
    (net (code "74") (name "unconnected-(LSM-Pad8)") (class "Default")
      (node (ref "LSM") (pin "8") (pinfunction "8_8") (pintype "passive"))
    )
    (net (code "75") (name "unconnected-(LSM-Pad9)") (class "Default")
      (node (ref "LSM") (pin "9") (pinfunction "9_9") (pintype "passive"))
    )
    (net (code "76") (name "unconnected-(U$1-P$9_PIO(4)-PadP$9)") (class "Default")
      (node (ref "U$1") (pin "P$9") (pinfunction "P$9_PIO(4)_P$9") (pintype "bidirectional"))
    )
    (net (code "77") (name "unconnected-(U$1-P$16_RESET-PadP$16)") (class "Default")
      (node (ref "U$1") (pin "P$16") (pinfunction "P$16_RESET_P$16") (pintype "input"))
    )
    (net (code "78") (name "unconnected-(U$1-P$28_UART-RTS-PadP$28)") (class "Default")
      (node (ref "U$1") (pin "P$28") (pinfunction "P$28_UART-RTS_P$28") (pintype "output"))
    )
    (net (code "79") (name "unconnected-(U$1-P$30_UART-CTS-PadP$30)") (class "Default")
      (node (ref "U$1") (pin "P$30") (pinfunction "P$30_UART-CTS_P$30") (pintype "input"))
    )
  )
)
